# atmega32U4.net
KiCad netlist of a schematic drawn in EAGLE
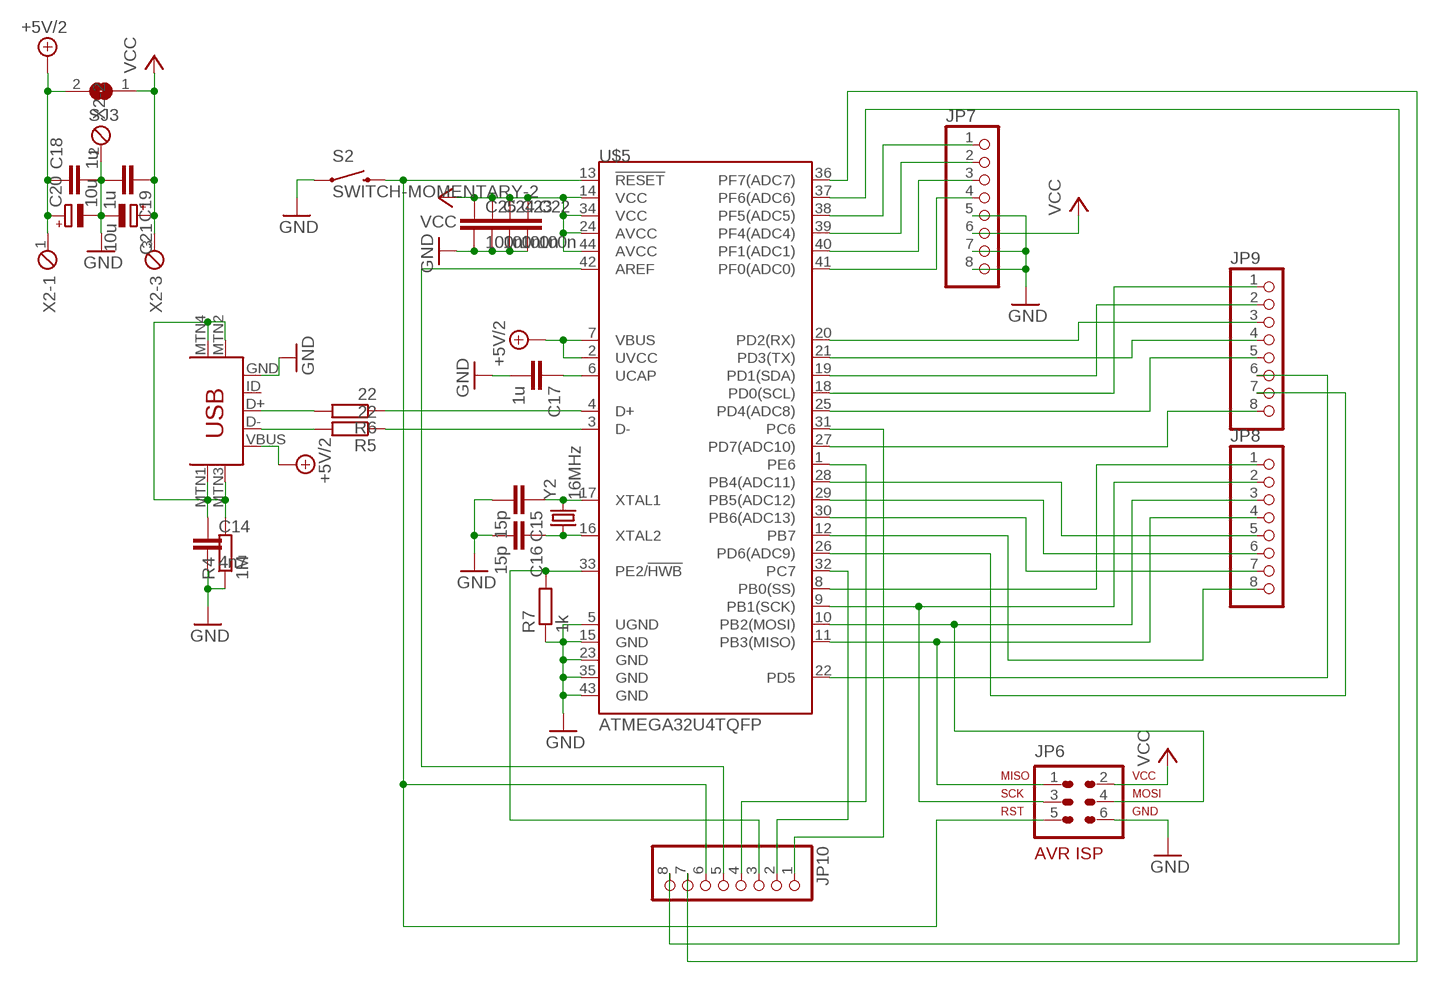
[diagram p0: schematic, sheet 1]

(export (version "E")
  (design (tool "Eeschema 10.0.6"))
  (components
    (comp (ref "C14")
      (value "4n7")
      (footprint "eagle-import:C0603")
      (libsource (lib "eagle-import") (part "C-EUC0603"))
    )
    (comp (ref "C15")
      (value "15p")
      (footprint "eagle-import:C0603")
      (libsource (lib "eagle-import") (part "C-EUC0603"))
    )
    (comp (ref "C16")
      (value "15p")
      (footprint "eagle-import:C0603")
      (libsource (lib "eagle-import") (part "C-EUC0603"))
    )
    (comp (ref "C17")
      (value "1u")
      (footprint "eagle-import:C0603")
      (libsource (lib "eagle-import") (part "C-EUC0603"))
    )
    (comp (ref "C18")
      (value "1u")
      (footprint "eagle-import:C0805")
      (libsource (lib "eagle-import") (part "C-EUC0805"))
    )
    (comp (ref "C19")
      (value "1u")
      (footprint "eagle-import:C0805")
      (libsource (lib "eagle-import") (part "C-EUC0805"))
    )
    (comp (ref "C20")
      (value "10u")
      (footprint "eagle-import:SMC_B")
      (libsource (lib "eagle-import") (part "CPOL-EUSMCB"))
    )
    (comp (ref "C21")
      (value "10u")
      (footprint "eagle-import:SMC_B")
      (libsource (lib "eagle-import") (part "CPOL-EUSMCB"))
    )
    (comp (ref "C22")
      (value "100n")
      (footprint "eagle-import:C0603")
      (libsource (lib "eagle-import") (part "C-EUC0603"))
    )
    (comp (ref "C23")
      (value "100n")
      (footprint "eagle-import:C0603")
      (libsource (lib "eagle-import") (part "C-EUC0603"))
    )
    (comp (ref "C24")
      (value "100n")
      (footprint "eagle-import:C0603")
      (libsource (lib "eagle-import") (part "C-EUC0603"))
    )
    (comp (ref "C25")
      (value "100n")
      (footprint "eagle-import:C0603")
      (libsource (lib "eagle-import") (part "C-EUC0603"))
    )
    (comp (ref "JP6")
      (value "AVR-ISP-6VERT")
      (footprint "eagle-import:AVR-ISP-6")
      (libsource (lib "eagle-import") (part "AVR-ISP-6VERT"))
    )
    (comp (ref "JP7")
      (value "PINHD_FIXEDPAD_ROUND-1X8")
      (footprint "eagle-import:1X08_ROUND")
      (libsource (lib "eagle-import") (part "PINHD_FIXEDPAD_ROUND-1X8"))
    )
    (comp (ref "JP8")
      (value "PINHD_FIXEDPAD_ROUND-1X8")
      (footprint "eagle-import:1X08_ROUND")
      (libsource (lib "eagle-import") (part "PINHD_FIXEDPAD_ROUND-1X8"))
    )
    (comp (ref "JP9")
      (value "PINHD_FIXEDPAD_ROUND-1X8")
      (footprint "eagle-import:1X08_ROUND")
      (libsource (lib "eagle-import") (part "PINHD_FIXEDPAD_ROUND-1X8"))
    )
    (comp (ref "JP10")
      (value "PINHD_FIXEDPAD_ROUND-1X8")
      (footprint "eagle-import:1X08_ROUND")
      (libsource (lib "eagle-import") (part "PINHD_FIXEDPAD_ROUND-1X8"))
    )
    (comp (ref "R4")
      (value "1M")
      (footprint "eagle-import:R0603")
      (libsource (lib "eagle-import") (part "R-EU_R0603"))
    )
    (comp (ref "R5")
      (value "22")
      (footprint "eagle-import:R0603")
      (libsource (lib "eagle-import") (part "R-EU_R0603"))
    )
    (comp (ref "R6")
      (value "22")
      (footprint "eagle-import:R0603")
      (libsource (lib "eagle-import") (part "R-EU_R0603"))
    )
    (comp (ref "R7")
      (value "1k")
      (footprint "eagle-import:R0603")
      (libsource (lib "eagle-import") (part "R-EU_R0603"))
    )
    (comp (ref "S2")
      (value "SWITCH-MOMENTARY-2")
      (footprint "eagle-import:TACTILE_SWITCH_TALL")
      (libsource (lib "eagle-import") (part "SWITCH-MOMENTARY-2"))
    )
    (comp (ref "SJ3")
      (value "SJ_SMALL")
      (footprint "eagle-import:SJ_2S-NO")
      (libsource (lib "eagle-import") (part "SJ_SMALL"))
    )
    (comp (ref "U$3")
      (value "USB-MINIB-5PIN")
      (footprint "eagle-import:USB-MINIB")
      (libsource (lib "eagle-import") (part "USB-MINIB-5PIN"))
    )
    (comp (ref "U$5")
      (value "ATMEGA32U4TQFP")
      (footprint "eagle-import:TQFP44")
      (libsource (lib "eagle-import") (part "ATMEGA32U4TQFP"))
    )
    (comp (ref "X2")
      (value "MPT3")
      (footprint "eagle-import:3POL254")
      (libsource (lib "eagle-import") (part "MPT3"))
    )
    (comp (ref "Y2")
      (value "16MHz")
      (footprint "eagle-import:CRYSTAL-SMD-5X3")
      (libsource (lib "eagle-import") (part "CRYSTAL5X3"))
    )
  )
  (nets
    (net (code "1") (name "+5V{slash}2") (class "Default")
      (node (ref "C18") (pin "1") (pinfunction "1_1") (pintype "passive"))
      (node (ref "C20") (pin "+") (pinfunction "+_+") (pintype "passive"))
      (node (ref "SJ3") (pin "2") (pinfunction "2_2") (pintype "passive"))
      (node (ref "U$3") (pin "VBUS") (pinfunction "VBUS_VBUS") (pintype "bidirectional"))
      (node (ref "U$5") (pin "2") (pinfunction "UVCC_2") (pintype "bidirectional"))
      (node (ref "U$5") (pin "7") (pinfunction "VBUS_7") (pintype "bidirectional"))
      (node (ref "X2") (pin "1") (pinfunction "1_1") (pintype "passive"))
    )
    (net (code "2") (name "GND") (class "Default")
      (node (ref "C14") (pin "2") (pinfunction "2_2") (pintype "passive"))
      (node (ref "C15") (pin "2") (pinfunction "2_2") (pintype "passive"))
      (node (ref "C16") (pin "2") (pinfunction "2_2") (pintype "passive"))
      (node (ref "C17") (pin "2") (pinfunction "2_2") (pintype "passive"))
      (node (ref "C18") (pin "2") (pinfunction "2_2") (pintype "passive"))
      (node (ref "C19") (pin "2") (pinfunction "2_2") (pintype "passive"))
      (node (ref "C20") (pin "-") (pinfunction "-_-") (pintype "passive"))
      (node (ref "C21") (pin "-") (pinfunction "-_-") (pintype "passive"))
      (node (ref "C22") (pin "2") (pinfunction "2_2") (pintype "passive"))
      (node (ref "C23") (pin "2") (pinfunction "2_2") (pintype "passive"))
      (node (ref "C24") (pin "2") (pinfunction "2_2") (pintype "passive"))
      (node (ref "C25") (pin "2") (pinfunction "2_2") (pintype "passive"))
      (node (ref "JP6") (pin "6") (pinfunction "6_6") (pintype "passive"))
      (node (ref "JP7") (pin "5") (pinfunction "5_5") (pintype "passive"))
      (node (ref "JP7") (pin "7") (pinfunction "7_7") (pintype "passive"))
      (node (ref "JP7") (pin "8") (pinfunction "8_8") (pintype "passive"))
      (node (ref "R4") (pin "1") (pinfunction "1_1") (pintype "passive"))
      (node (ref "R7") (pin "1") (pinfunction "1_1") (pintype "passive"))
      (node (ref "S2") (pin "A2") (pinfunction "1_A2") (pintype "passive"))
      (node (ref "U$3") (pin "GND") (pinfunction "GND_GND") (pintype "bidirectional"))
      (node (ref "U$5") (pin "15") (pinfunction "GND_15") (pintype "bidirectional"))
      (node (ref "U$5") (pin "23") (pinfunction "GND_23") (pintype "bidirectional"))
      (node (ref "U$5") (pin "35") (pinfunction "GND_35") (pintype "bidirectional"))
      (node (ref "U$5") (pin "43") (pinfunction "GND_43") (pintype "bidirectional"))
      (node (ref "U$5") (pin "5") (pinfunction "UGND_5") (pintype "bidirectional"))
      (node (ref "X2") (pin "2") (pinfunction "1_2") (pintype "passive"))
    )
    (net (code "3") (name "Net-(R5-Pad2)") (class "Default")
      (node (ref "R5") (pin "2") (pinfunction "2_2") (pintype "passive"))
      (node (ref "U$3") (pin "D-") (pinfunction "D-_D-") (pintype "bidirectional"))
    )
    (net (code "4") (name "Net-(R6-Pad2)") (class "Default")
      (node (ref "R6") (pin "2") (pinfunction "2_2") (pintype "passive"))
      (node (ref "U$3") (pin "D+") (pinfunction "D+_D+") (pintype "bidirectional"))
    )
    (net (code "5") (name "Net-(S2-2)") (class "Default")
      (node (ref "JP10") (pin "6") (pinfunction "6_6") (pintype "passive"))
      (node (ref "JP6") (pin "5") (pinfunction "5_5") (pintype "passive"))
      (node (ref "S2") (pin "B2") (pinfunction "2_B2") (pintype "passive"))
      (node (ref "U$5") (pin "13") (pinfunction "~{RESET}_13") (pintype "bidirectional"))
    )
    (net (code "6") (name "Net-(U$3-MTN1)") (class "Default")
      (node (ref "C14") (pin "1") (pinfunction "1_1") (pintype "passive"))
      (node (ref "R4") (pin "2") (pinfunction "2_2") (pintype "passive"))
      (node (ref "U$3") (pin "MTN1") (pinfunction "MTN2_MTN1") (pintype "bidirectional"))
      (node (ref "U$3") (pin "MTN2") (pinfunction "MTN3_MTN2") (pintype "bidirectional"))
      (node (ref "U$3") (pin "MTN3") (pinfunction "MTN1_MTN3") (pintype "bidirectional"))
      (node (ref "U$3") (pin "MTN4") (pinfunction "MTN4_MTN4") (pintype "bidirectional"))
    )
    (net (code "7") (name "Net-(U$5-AREF)") (class "Default")
      (node (ref "JP10") (pin "5") (pinfunction "5_5") (pintype "passive"))
      (node (ref "U$5") (pin "42") (pinfunction "AREF_42") (pintype "bidirectional"))
    )
    (net (code "8") (name "Net-(U$5-D+)") (class "Default")
      (node (ref "R6") (pin "1") (pinfunction "1_1") (pintype "passive"))
      (node (ref "U$5") (pin "4") (pinfunction "D+_4") (pintype "bidirectional"))
    )
    (net (code "9") (name "Net-(U$5-D-)") (class "Default")
      (node (ref "R5") (pin "1") (pinfunction "1_1") (pintype "passive"))
      (node (ref "U$5") (pin "3") (pinfunction "D-_3") (pintype "bidirectional"))
    )
    (net (code "10") (name "Net-(U$5-PB0(SS))") (class "Default")
      (node (ref "JP8") (pin "1") (pinfunction "1_1") (pintype "passive"))
      (node (ref "U$5") (pin "8") (pinfunction "PB0(SS)_8") (pintype "bidirectional"))
    )
    (net (code "11") (name "Net-(U$5-PB1(SCK))") (class "Default")
      (node (ref "JP6") (pin "3") (pinfunction "3_3") (pintype "passive"))
      (node (ref "JP8") (pin "2") (pinfunction "2_2") (pintype "passive"))
      (node (ref "U$5") (pin "9") (pinfunction "PB1(SCK)_9") (pintype "bidirectional"))
    )
    (net (code "12") (name "Net-(U$5-PB2(MOSI))") (class "Default")
      (node (ref "JP6") (pin "4") (pinfunction "4_4") (pintype "passive"))
      (node (ref "JP8") (pin "3") (pinfunction "3_3") (pintype "passive"))
      (node (ref "U$5") (pin "10") (pinfunction "PB2(MOSI)_10") (pintype "bidirectional"))
    )
    (net (code "13") (name "Net-(U$5-PB3(MISO))") (class "Default")
      (node (ref "JP6") (pin "1") (pinfunction "1_1") (pintype "passive"))
      (node (ref "JP8") (pin "4") (pinfunction "4_4") (pintype "passive"))
      (node (ref "U$5") (pin "11") (pinfunction "PB3(MISO)_11") (pintype "bidirectional"))
    )
    (net (code "14") (name "Net-(U$5-PB4(ADC11))") (class "Default")
      (node (ref "JP8") (pin "5") (pinfunction "5_5") (pintype "passive"))
      (node (ref "U$5") (pin "28") (pinfunction "PB4(ADC11)_28") (pintype "bidirectional"))
    )
    (net (code "15") (name "Net-(U$5-PB5(ADC12))") (class "Default")
      (node (ref "JP8") (pin "6") (pinfunction "6_6") (pintype "passive"))
      (node (ref "U$5") (pin "29") (pinfunction "PB5(ADC12)_29") (pintype "bidirectional"))
    )
    (net (code "16") (name "Net-(U$5-PB6(ADC13))") (class "Default")
      (node (ref "JP8") (pin "7") (pinfunction "7_7") (pintype "passive"))
      (node (ref "U$5") (pin "30") (pinfunction "PB6(ADC13)_30") (pintype "bidirectional"))
    )
    (net (code "17") (name "Net-(U$5-PB7)") (class "Default")
      (node (ref "JP8") (pin "8") (pinfunction "8_8") (pintype "passive"))
      (node (ref "U$5") (pin "12") (pinfunction "PB7_12") (pintype "bidirectional"))
    )
    (net (code "18") (name "Net-(U$5-PC6)") (class "Default")
      (node (ref "JP10") (pin "1") (pinfunction "1_1") (pintype "passive"))
      (node (ref "U$5") (pin "31") (pinfunction "PC6_31") (pintype "bidirectional"))
    )
    (net (code "19") (name "Net-(U$5-PC7)") (class "Default")
      (node (ref "JP10") (pin "2") (pinfunction "2_2") (pintype "passive"))
      (node (ref "U$5") (pin "32") (pinfunction "PC7_32") (pintype "bidirectional"))
    )
    (net (code "20") (name "Net-(U$5-PD0(SCL))") (class "Default")
      (node (ref "JP9") (pin "1") (pinfunction "1_1") (pintype "passive"))
      (node (ref "U$5") (pin "18") (pinfunction "PD0(SCL)_18") (pintype "bidirectional"))
    )
    (net (code "21") (name "Net-(U$5-PD1(SDA))") (class "Default")
      (node (ref "JP9") (pin "2") (pinfunction "2_2") (pintype "passive"))
      (node (ref "U$5") (pin "19") (pinfunction "PD1(SDA)_19") (pintype "bidirectional"))
    )
    (net (code "22") (name "Net-(U$5-PD2(RX))") (class "Default")
      (node (ref "JP9") (pin "3") (pinfunction "3_3") (pintype "passive"))
      (node (ref "U$5") (pin "20") (pinfunction "PD2(RX)_20") (pintype "bidirectional"))
    )
    (net (code "23") (name "Net-(U$5-PD3(TX))") (class "Default")
      (node (ref "JP9") (pin "4") (pinfunction "4_4") (pintype "passive"))
      (node (ref "U$5") (pin "21") (pinfunction "PD3(TX)_21") (pintype "bidirectional"))
    )
    (net (code "24") (name "Net-(U$5-PD4(ADC8))") (class "Default")
      (node (ref "JP9") (pin "5") (pinfunction "5_5") (pintype "passive"))
      (node (ref "U$5") (pin "25") (pinfunction "PD4(ADC8)_25") (pintype "bidirectional"))
    )
    (net (code "25") (name "Net-(U$5-PD5)") (class "Default")
      (node (ref "JP9") (pin "6") (pinfunction "6_6") (pintype "passive"))
      (node (ref "U$5") (pin "22") (pinfunction "PD5_22") (pintype "bidirectional"))
    )
    (net (code "26") (name "Net-(U$5-PD6(ADC9))") (class "Default")
      (node (ref "JP9") (pin "7") (pinfunction "7_7") (pintype "passive"))
      (node (ref "U$5") (pin "26") (pinfunction "PD6(ADC9)_26") (pintype "bidirectional"))
    )
    (net (code "27") (name "Net-(U$5-PD7(ADC10))") (class "Default")
      (node (ref "JP9") (pin "8") (pinfunction "8_8") (pintype "passive"))
      (node (ref "U$5") (pin "27") (pinfunction "PD7(ADC10)_27") (pintype "bidirectional"))
    )
    (net (code "28") (name "Net-(U$5-PE2{slash}~{HWB})") (class "Default")
      (node (ref "JP10") (pin "3") (pinfunction "3_3") (pintype "passive"))
      (node (ref "R7") (pin "2") (pinfunction "2_2") (pintype "passive"))
      (node (ref "U$5") (pin "33") (pinfunction "PE2/~{HWB}_33") (pintype "bidirectional"))
    )
    (net (code "29") (name "Net-(U$5-PE6)") (class "Default")
      (node (ref "JP10") (pin "4") (pinfunction "4_4") (pintype "passive"))
      (node (ref "U$5") (pin "1") (pinfunction "PE6_1") (pintype "bidirectional"))
    )
    (net (code "30") (name "Net-(U$5-PF0(ADC0))") (class "Default")
      (node (ref "JP7") (pin "4") (pinfunction "4_4") (pintype "passive"))
      (node (ref "U$5") (pin "41") (pinfunction "PF0(ADC0)_41") (pintype "bidirectional"))
    )
    (net (code "31") (name "Net-(U$5-PF1(ADC1))") (class "Default")
      (node (ref "JP7") (pin "3") (pinfunction "3_3") (pintype "passive"))
      (node (ref "U$5") (pin "40") (pinfunction "PF1(ADC1)_40") (pintype "bidirectional"))
    )
    (net (code "32") (name "Net-(U$5-PF4(ADC4))") (class "Default")
      (node (ref "JP7") (pin "2") (pinfunction "2_2") (pintype "passive"))
      (node (ref "U$5") (pin "39") (pinfunction "PF4(ADC4)_39") (pintype "bidirectional"))
    )
    (net (code "33") (name "Net-(U$5-PF5(ADC5))") (class "Default")
      (node (ref "JP7") (pin "1") (pinfunction "1_1") (pintype "passive"))
      (node (ref "U$5") (pin "38") (pinfunction "PF5(ADC5)_38") (pintype "bidirectional"))
    )
    (net (code "34") (name "Net-(U$5-PF6(ADC6))") (class "Default")
      (node (ref "JP10") (pin "8") (pinfunction "8_8") (pintype "passive"))
      (node (ref "U$5") (pin "37") (pinfunction "PF6(ADC6)_37") (pintype "bidirectional"))
    )
    (net (code "35") (name "Net-(U$5-PF7(ADC7))") (class "Default")
      (node (ref "JP10") (pin "7") (pinfunction "7_7") (pintype "passive"))
      (node (ref "U$5") (pin "36") (pinfunction "PF7(ADC7)_36") (pintype "bidirectional"))
    )
    (net (code "36") (name "Net-(U$5-UCAP)") (class "Default")
      (node (ref "C17") (pin "1") (pinfunction "1_1") (pintype "passive"))
      (node (ref "U$5") (pin "6") (pinfunction "UCAP_6") (pintype "bidirectional"))
    )
    (net (code "37") (name "Net-(U$5-XTAL1)") (class "Default")
      (node (ref "C15") (pin "1") (pinfunction "1_1") (pintype "passive"))
      (node (ref "U$5") (pin "17") (pinfunction "XTAL1_17") (pintype "bidirectional"))
      (node (ref "Y2") (pin "3") (pinfunction "2_3") (pintype "passive"))
    )
    (net (code "38") (name "Net-(U$5-XTAL2)") (class "Default")
      (node (ref "C16") (pin "1") (pinfunction "1_1") (pintype "passive"))
      (node (ref "U$5") (pin "16") (pinfunction "XTAL2_16") (pintype "bidirectional"))
      (node (ref "Y2") (pin "1") (pinfunction "1_1") (pintype "passive"))
    )
    (net (code "39") (name "VCC") (class "Default")
      (node (ref "C19") (pin "1") (pinfunction "1_1") (pintype "passive"))
      (node (ref "C21") (pin "+") (pinfunction "+_+") (pintype "passive"))
      (node (ref "C22") (pin "1") (pinfunction "1_1") (pintype "passive"))
      (node (ref "C23") (pin "1") (pinfunction "1_1") (pintype "passive"))
      (node (ref "C24") (pin "1") (pinfunction "1_1") (pintype "passive"))
      (node (ref "C25") (pin "1") (pinfunction "1_1") (pintype "passive"))
      (node (ref "JP6") (pin "2") (pinfunction "2_2") (pintype "passive"))
      (node (ref "JP7") (pin "6") (pinfunction "6_6") (pintype "passive"))
      (node (ref "SJ3") (pin "1") (pinfunction "1_1") (pintype "passive"))
      (node (ref "U$5") (pin "14") (pinfunction "VCC_14") (pintype "bidirectional"))
      (node (ref "U$5") (pin "24") (pinfunction "AVCC_24") (pintype "bidirectional"))
      (node (ref "U$5") (pin "34") (pinfunction "VCC_34") (pintype "bidirectional"))
      (node (ref "U$5") (pin "44") (pinfunction "AVCC_44") (pintype "bidirectional"))
      (node (ref "X2") (pin "3") (pinfunction "1_3") (pintype "passive"))
    )
    (net (code "40") (name "unconnected-(U$3-PadID)") (class "Default")
      (node (ref "U$3") (pin "ID") (pinfunction "ID_ID") (pintype "bidirectional"))
    )
  )
)
